# motoko_ice_dragon_x_dc.net
KiCad netlist of a schematic drawn in EAGLE
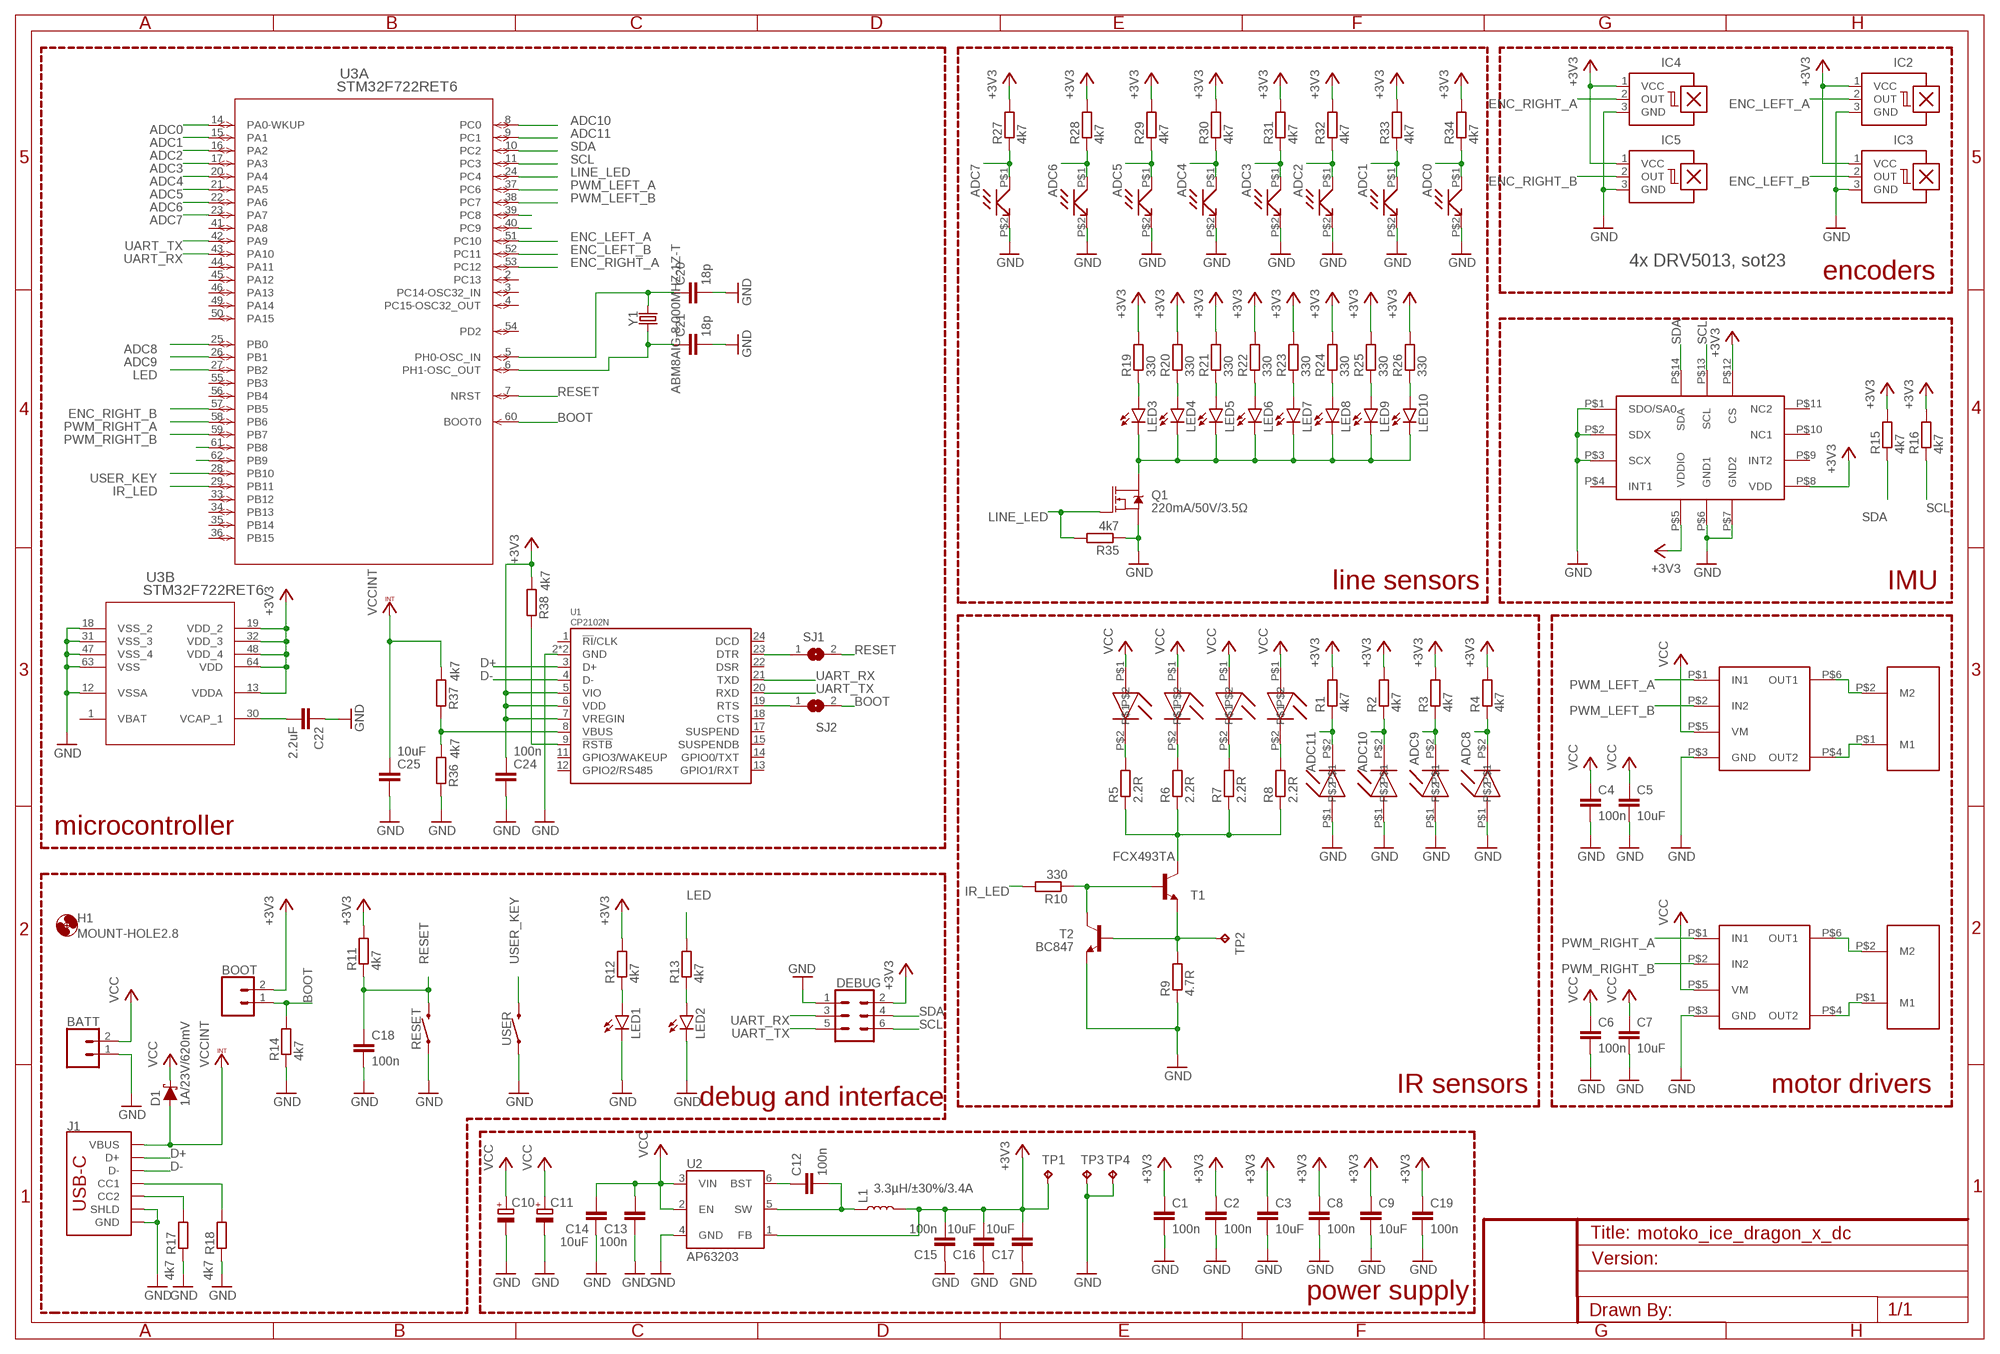
[diagram p0: schematic, sheet 1]

(export (version "E")
  (design (tool "Eeschema 10.0.6"))
  (components
    (comp (ref "BATT")
      (value "CONN_02LOCK_LONGPADS")
      (footprint "eagle-import:1X02_LOCK_LONGPADS")
      (libsource (lib "eagle-import") (part "CONN_02LOCK_LONGPADS"))
    )
    (comp (ref "BOOT")
      (value "CONN_02LOCK_LONGPADS")
      (footprint "eagle-import:1X02_LOCK_LONGPADS")
      (libsource (lib "eagle-import") (part "CONN_02LOCK_LONGPADS"))
    )
    (comp (ref "C1")
      (value "100n")
      (footprint "eagle-import:C0805")
      (libsource (lib "eagle-import") (part "C-EUC0805"))
    )
    (comp (ref "C2")
      (value "100n")
      (footprint "eagle-import:C0805")
      (libsource (lib "eagle-import") (part "C-EUC0805"))
    )
    (comp (ref "C3")
      (value "10uF")
      (footprint "eagle-import:C0805")
      (libsource (lib "eagle-import") (part "C-EUC0805"))
    )
    (comp (ref "C4")
      (value "100n")
      (footprint "eagle-import:C0805")
      (libsource (lib "eagle-import") (part "C-EUC0805"))
    )
    (comp (ref "C5")
      (value "10uF")
      (footprint "eagle-import:C0805")
      (libsource (lib "eagle-import") (part "C-EUC0805"))
    )
    (comp (ref "C6")
      (value "100n")
      (footprint "eagle-import:C0805")
      (libsource (lib "eagle-import") (part "C-EUC0805"))
    )
    (comp (ref "C7")
      (value "10uF")
      (footprint "eagle-import:C0805")
      (libsource (lib "eagle-import") (part "C-EUC0805"))
    )
    (comp (ref "C8")
      (value "100n")
      (footprint "eagle-import:C0805")
      (libsource (lib "eagle-import") (part "C-EUC0805"))
    )
    (comp (ref "C9")
      (value "10uF")
      (footprint "eagle-import:C0805")
      (libsource (lib "eagle-import") (part "C-EUC0805"))
    )
    (comp (ref "C10")
      (value "CPOL-EU140CLH-0810")
      (footprint "eagle-import:140CLH-0810")
      (libsource (lib "eagle-import") (part "CPOL-EU140CLH-0810"))
    )
    (comp (ref "C11")
      (value "CPOL-EU140CLH-0810")
      (footprint "eagle-import:140CLH-0810")
      (libsource (lib "eagle-import") (part "CPOL-EU140CLH-0810"))
    )
    (comp (ref "C12")
      (value "100n")
      (footprint "eagle-import:C0805")
      (libsource (lib "eagle-import") (part "C-EUC0805"))
    )
    (comp (ref "C13")
      (value "100n")
      (footprint "eagle-import:C0805")
      (libsource (lib "eagle-import") (part "C-EUC0805"))
    )
    (comp (ref "C14")
      (value "10uF")
      (footprint "eagle-import:C0805")
      (libsource (lib "eagle-import") (part "C-EUC0805"))
    )
    (comp (ref "C15")
      (value "100n")
      (footprint "eagle-import:C0805")
      (libsource (lib "eagle-import") (part "C-EUC0805"))
    )
    (comp (ref "C16")
      (value "10uF")
      (footprint "eagle-import:C0805")
      (libsource (lib "eagle-import") (part "C-EUC0805"))
    )
    (comp (ref "C17")
      (value "10uF")
      (footprint "eagle-import:C0805")
      (libsource (lib "eagle-import") (part "C-EUC0805"))
    )
    (comp (ref "C18")
      (value "100n")
      (footprint "eagle-import:C0805")
      (libsource (lib "eagle-import") (part "C-EUC0805"))
    )
    (comp (ref "C19")
      (value "100n")
      (footprint "eagle-import:C0805")
      (libsource (lib "eagle-import") (part "C-EUC0805"))
    )
    (comp (ref "C20")
      (value "18p")
      (footprint "eagle-import:C0805")
      (libsource (lib "eagle-import") (part "C-EUC0805"))
    )
    (comp (ref "C21")
      (value "18p")
      (footprint "eagle-import:C0805")
      (libsource (lib "eagle-import") (part "C-EUC0805"))
    )
    (comp (ref "C22")
      (value "2.2uF")
      (footprint "eagle-import:C0805")
      (libsource (lib "eagle-import") (part "C-EUC0805"))
    )
    (comp (ref "C24")
      (value "100n")
      (footprint "eagle-import:C0805")
      (libsource (lib "eagle-import") (part "C-EUC0805"))
    )
    (comp (ref "C25")
      (value "10uF")
      (footprint "eagle-import:C0805")
      (libsource (lib "eagle-import") (part "C-EUC0805"))
    )
    (comp (ref "D1")
      (value "1A/23V/620mV")
      (footprint "eagle-import:SOD-323")
      (libsource (lib "eagle-import") (part "DIODE-SCHOTTKY-BAT20J"))
    )
    (comp (ref "DEBUG")
      (value "FEMALE 2x3")
      (footprint "eagle-import:2X3")
      (libsource (lib "eagle-import") (part "CONN_03X2FEMALE"))
    )
    (comp (ref "H1")
      (value "MOUNT-HOLE2.8")
      (footprint "eagle-import:2,8")
      (libsource (lib "eagle-import") (part "MOUNT-HOLE2.8"))
    )
    (comp (ref "IC2")
      (value "A1202LH")
      (footprint "eagle-import:SOT23-W")
      (libsource (lib "eagle-import") (part "A12?LH02"))
    )
    (comp (ref "IC3")
      (value "A1202LH")
      (footprint "eagle-import:SOT23-W")
      (libsource (lib "eagle-import") (part "A12?LH02"))
    )
    (comp (ref "IC4")
      (value "A1202LH")
      (footprint "eagle-import:SOT23-W")
      (libsource (lib "eagle-import") (part "A12?LH02"))
    )
    (comp (ref "IC5")
      (value "A1202LH")
      (footprint "eagle-import:SOT23-W")
      (libsource (lib "eagle-import") (part "A12?LH02"))
    )
    (comp (ref "J1")
      (value "640-USB4105-GF-A-120, man. GCT")
      (footprint "eagle-import:USB-C-16P-2LAYER-PADS")
      (libsource (lib "eagle-import") (part "USB_C_2-LAYER_PADS"))
    )
    (comp (ref "L1")
      (value "3.3µH/±30%/3.4A")
      (footprint "eagle-import:CR54")
      (libsource (lib "eagle-import") (part "INDUCTOR-CR54-3.3UH"))
    )
    (comp (ref "LED1")
      (value "LEDCHIPLED_1206")
      (footprint "eagle-import:CHIPLED_1206")
      (libsource (lib "eagle-import") (part "LEDCHIPLED_1206"))
    )
    (comp (ref "LED2")
      (value "LEDCHIPLED_1206")
      (footprint "eagle-import:CHIPLED_1206")
      (libsource (lib "eagle-import") (part "LEDCHIPLED_1206"))
    )
    (comp (ref "LED3")
      (value "LEDCHIPLED_1206")
      (footprint "eagle-import:CHIPLED_1206")
      (libsource (lib "eagle-import") (part "LEDCHIPLED_1206"))
    )
    (comp (ref "LED4")
      (value "LEDCHIPLED_1206")
      (footprint "eagle-import:CHIPLED_1206")
      (libsource (lib "eagle-import") (part "LEDCHIPLED_1206"))
    )
    (comp (ref "LED5")
      (value "LEDCHIPLED_1206")
      (footprint "eagle-import:CHIPLED_1206")
      (libsource (lib "eagle-import") (part "LEDCHIPLED_1206"))
    )
    (comp (ref "LED6")
      (value "LEDCHIPLED_1206")
      (footprint "eagle-import:CHIPLED_1206")
      (libsource (lib "eagle-import") (part "LEDCHIPLED_1206"))
    )
    (comp (ref "LED7")
      (value "LEDCHIPLED_1206")
      (footprint "eagle-import:CHIPLED_1206")
      (libsource (lib "eagle-import") (part "LEDCHIPLED_1206"))
    )
    (comp (ref "LED8")
      (value "LEDCHIPLED_1206")
      (footprint "eagle-import:CHIPLED_1206")
      (libsource (lib "eagle-import") (part "LEDCHIPLED_1206"))
    )
    (comp (ref "LED9")
      (value "LEDCHIPLED_1206")
      (footprint "eagle-import:CHIPLED_1206")
      (libsource (lib "eagle-import") (part "LEDCHIPLED_1206"))
    )
    (comp (ref "LED10")
      (value "LEDCHIPLED_1206")
      (footprint "eagle-import:CHIPLED_1206")
      (libsource (lib "eagle-import") (part "LEDCHIPLED_1206"))
    )
    (comp (ref "Q1")
      (value "220mA/50V/3.5Ω")
      (footprint "eagle-import:SOT23-3")
      (libsource (lib "eagle-import") (part "MOSFET-NCH-BSS138"))
    )
    (comp (ref "R1")
      (value "4k7")
      (footprint "eagle-import:M0805")
      (libsource (lib "eagle-import") (part "R-EU_M0805"))
    )
    (comp (ref "R2")
      (value "4k7")
      (footprint "eagle-import:M0805")
      (libsource (lib "eagle-import") (part "R-EU_M0805"))
    )
    (comp (ref "R3")
      (value "4k7")
      (footprint "eagle-import:M0805")
      (libsource (lib "eagle-import") (part "R-EU_M0805"))
    )
    (comp (ref "R4")
      (value "4k7")
      (footprint "eagle-import:M0805")
      (libsource (lib "eagle-import") (part "R-EU_M0805"))
    )
    (comp (ref "R5")
      (value "2.2R")
      (footprint "eagle-import:M0805")
      (libsource (lib "eagle-import") (part "R-EU_M0805"))
    )
    (comp (ref "R6")
      (value "2.2R")
      (footprint "eagle-import:M0805")
      (libsource (lib "eagle-import") (part "R-EU_M0805"))
    )
    (comp (ref "R7")
      (value "2.2R")
      (footprint "eagle-import:M0805")
      (libsource (lib "eagle-import") (part "R-EU_M0805"))
    )
    (comp (ref "R8")
      (value "2.2R")
      (footprint "eagle-import:M0805")
      (libsource (lib "eagle-import") (part "R-EU_M0805"))
    )
    (comp (ref "R9")
      (value "4.7R")
      (footprint "eagle-import:M0805")
      (libsource (lib "eagle-import") (part "R-EU_M0805"))
    )
    (comp (ref "R10")
      (value "330")
      (footprint "eagle-import:M0805")
      (libsource (lib "eagle-import") (part "R-EU_M0805"))
    )
    (comp (ref "R11")
      (value "4k7")
      (footprint "eagle-import:M0805")
      (libsource (lib "eagle-import") (part "R-EU_M0805"))
    )
    (comp (ref "R12")
      (value "4k7")
      (footprint "eagle-import:M0805")
      (libsource (lib "eagle-import") (part "R-EU_M0805"))
    )
    (comp (ref "R13")
      (value "4k7")
      (footprint "eagle-import:M0805")
      (libsource (lib "eagle-import") (part "R-EU_M0805"))
    )
    (comp (ref "R14")
      (value "4k7")
      (footprint "eagle-import:M0805")
      (libsource (lib "eagle-import") (part "R-EU_M0805"))
    )
    (comp (ref "R15")
      (value "4k7")
      (footprint "eagle-import:M0805")
      (libsource (lib "eagle-import") (part "R-EU_M0805"))
    )
    (comp (ref "R16")
      (value "4k7")
      (footprint "eagle-import:M0805")
      (libsource (lib "eagle-import") (part "R-EU_M0805"))
    )
    (comp (ref "R17")
      (value "4k7")
      (footprint "eagle-import:M0805")
      (libsource (lib "eagle-import") (part "R-EU_M0805"))
    )
    (comp (ref "R18")
      (value "4k7")
      (footprint "eagle-import:M0805")
      (libsource (lib "eagle-import") (part "R-EU_M0805"))
    )
    (comp (ref "R19")
      (value "330")
      (footprint "eagle-import:M0805")
      (libsource (lib "eagle-import") (part "R-EU_M0805"))
    )
    (comp (ref "R20")
      (value "330")
      (footprint "eagle-import:M0805")
      (libsource (lib "eagle-import") (part "R-EU_M0805"))
    )
    (comp (ref "R21")
      (value "330")
      (footprint "eagle-import:M0805")
      (libsource (lib "eagle-import") (part "R-EU_M0805"))
    )
    (comp (ref "R22")
      (value "330")
      (footprint "eagle-import:M0805")
      (libsource (lib "eagle-import") (part "R-EU_M0805"))
    )
    (comp (ref "R23")
      (value "330")
      (footprint "eagle-import:M0805")
      (libsource (lib "eagle-import") (part "R-EU_M0805"))
    )
    (comp (ref "R24")
      (value "330")
      (footprint "eagle-import:M0805")
      (libsource (lib "eagle-import") (part "R-EU_M0805"))
    )
    (comp (ref "R25")
      (value "330")
      (footprint "eagle-import:M0805")
      (libsource (lib "eagle-import") (part "R-EU_M0805"))
    )
    (comp (ref "R26")
      (value "330")
      (footprint "eagle-import:M0805")
      (libsource (lib "eagle-import") (part "R-EU_M0805"))
    )
    (comp (ref "R27")
      (value "4k7")
      (footprint "eagle-import:M0805")
      (libsource (lib "eagle-import") (part "R-EU_M0805"))
    )
    (comp (ref "R28")
      (value "4k7")
      (footprint "eagle-import:M0805")
      (libsource (lib "eagle-import") (part "R-EU_M0805"))
    )
    (comp (ref "R29")
      (value "4k7")
      (footprint "eagle-import:M0805")
      (libsource (lib "eagle-import") (part "R-EU_M0805"))
    )
    (comp (ref "R30")
      (value "4k7")
      (footprint "eagle-import:M0805")
      (libsource (lib "eagle-import") (part "R-EU_M0805"))
    )
    (comp (ref "R31")
      (value "4k7")
      (footprint "eagle-import:M0805")
      (libsource (lib "eagle-import") (part "R-EU_M0805"))
    )
    (comp (ref "R32")
      (value "4k7")
      (footprint "eagle-import:M0805")
      (libsource (lib "eagle-import") (part "R-EU_M0805"))
    )
    (comp (ref "R33")
      (value "4k7")
      (footprint "eagle-import:M0805")
      (libsource (lib "eagle-import") (part "R-EU_M0805"))
    )
    (comp (ref "R34")
      (value "4k7")
      (footprint "eagle-import:M0805")
      (libsource (lib "eagle-import") (part "R-EU_M0805"))
    )
    (comp (ref "R35")
      (value "4k7")
      (footprint "eagle-import:M0805")
      (libsource (lib "eagle-import") (part "R-EU_M0805"))
    )
    (comp (ref "R36")
      (value "4k7")
      (footprint "eagle-import:M0805")
      (libsource (lib "eagle-import") (part "R-EU_M0805"))
    )
    (comp (ref "R37")
      (value "4k7")
      (footprint "eagle-import:M0805")
      (libsource (lib "eagle-import") (part "R-EU_M0805"))
    )
    (comp (ref "R38")
      (value "4k7")
      (footprint "eagle-import:M0805")
      (libsource (lib "eagle-import") (part "R-EU_M0805"))
    )
    (comp (ref "RESET")
      (value "MOMENTARY-SWITCH-SPST-SMD-6.2MM-TALL")
      (footprint "eagle-import:TACTILE_SWITCH_SMD_6.2MM_TALL")
      (libsource (lib "eagle-import") (part "MOMENTARY-SWITCH-SPST-SMD-6.2MM-TALL"))
    )
    (comp (ref "SJ1") (value "SJ") (footprint "eagle-import:SJ") (libsource (lib "eagle-import") (part "SJ")))
    (comp (ref "SJ2") (value "SJ") (footprint "eagle-import:SJ") (libsource (lib "eagle-import") (part "SJ")))
    (comp (ref "T1")
      (value "FCX493TA")
      (footprint "eagle-import:SOT89-BCE")
      (libsource (lib "eagle-import") (part "-NPN-SOT89-BCE"))
    )
    (comp (ref "T2")
      (value "BC847")
      (footprint "eagle-import:SOT23")
      (libsource (lib "eagle-import") (part "BC847"))
    )
    (comp (ref "TP1")
      (value "TPB1,27")
      (footprint "eagle-import:B1,27")
      (libsource (lib "eagle-import") (part "TPB1,27"))
    )
    (comp (ref "TP2")
      (value "TPB1,27")
      (footprint "eagle-import:B1,27")
      (libsource (lib "eagle-import") (part "TPB1,27"))
    )
    (comp (ref "TP3")
      (value "TPB1,27")
      (footprint "eagle-import:B1,27")
      (libsource (lib "eagle-import") (part "TPB1,27"))
    )
    (comp (ref "TP4")
      (value "TPB1,27")
      (footprint "eagle-import:B1,27")
      (libsource (lib "eagle-import") (part "TPB1,27"))
    )
    (comp (ref "U$1")
      (value "DRV8212")
      (footprint "eagle-import:SOT_0.6MM")
      (libsource (lib "eagle-import") (part "DRV8212"))
    )
    (comp (ref "U$2")
      (value "SFH3710")
      (footprint "eagle-import:SFH710")
      (libsource (lib "eagle-import") (part "SFH3710"))
    )
    (comp (ref "U$3")
      (value "DRV8212")
      (footprint "eagle-import:SOT_0.6MM")
      (libsource (lib "eagle-import") (part "DRV8212"))
    )
    (comp (ref "U$4")
      (value "POLOLU_MICRO_METAL_GEAR_MOTOR")
      (footprint "eagle-import:POLOLU_MICRO_METAL_GEAR_MOTOR")
      (libsource (lib "eagle-import") (part "POLOLU_MICRO_METAL_GEAR_MOTOR"))
    )
    (comp (ref "U$5")
      (value "POLOLU_MICRO_METAL_GEAR_MOTOR")
      (footprint "eagle-import:POLOLU_MICRO_METAL_GEAR_MOTOR")
      (libsource (lib "eagle-import") (part "POLOLU_MICRO_METAL_GEAR_MOTOR"))
    )
    (comp (ref "U$6")
      (value "LSM6DSM")
      (footprint "eagle-import:LGA14L")
      (libsource (lib "eagle-import") (part "LSM6DSM"))
    )
    (comp (ref "U$7")
      (value "LED_5MM_AXIAL")
      (footprint "eagle-import:LED_5MM_AXIAL")
      (libsource (lib "eagle-import") (part "LED_5MM_AXIAL"))
    )
    (comp (ref "U$8")
      (value "LED_5MM_AXIAL")
      (footprint "eagle-import:LED_5MM_AXIAL")
      (libsource (lib "eagle-import") (part "LED_5MM_AXIAL"))
    )
    (comp (ref "U$9")
      (value "LED_5MM_AXIAL")
      (footprint "eagle-import:LED_5MM_AXIAL")
      (libsource (lib "eagle-import") (part "LED_5MM_AXIAL"))
    )
    (comp (ref "U$10")
      (value "LED_5MM_AXIAL")
      (footprint "eagle-import:LED_5MM_AXIAL")
      (libsource (lib "eagle-import") (part "LED_5MM_AXIAL"))
    )
    (comp (ref "U$11")
      (value "LED_5MM_AXIAL")
      (footprint "eagle-import:LED_5MM_AXIAL")
      (libsource (lib "eagle-import") (part "LED_5MM_AXIAL"))
    )
    (comp (ref "U$12")
      (value "LED_5MM_AXIAL")
      (footprint "eagle-import:LED_5MM_AXIAL")
      (fields (field (name "SPICEPREFIX") "B"))
      (libsource (lib "eagle-import") (part "LED_5MM_AXIAL"))
    )
    (comp (ref "U$13")
      (value "LED_5MM_AXIAL")
      (footprint "eagle-import:LED_5MM_AXIAL")
      (libsource (lib "eagle-import") (part "LED_5MM_AXIAL"))
    )
    (comp (ref "U$14")
      (value "LED_5MM_AXIAL")
      (footprint "eagle-import:LED_5MM_AXIAL")
      (libsource (lib "eagle-import") (part "LED_5MM_AXIAL"))
    )
    (comp (ref "U$15")
      (value "SFH3710")
      (footprint "eagle-import:SFH710")
      (libsource (lib "eagle-import") (part "SFH3710"))
    )
    (comp (ref "U$16")
      (value "SFH3710")
      (footprint "eagle-import:SFH710")
      (libsource (lib "eagle-import") (part "SFH3710"))
    )
    (comp (ref "U$17")
      (value "SFH3710")
      (footprint "eagle-import:SFH710")
      (libsource (lib "eagle-import") (part "SFH3710"))
    )
    (comp (ref "U$18")
      (value "SFH3710")
      (footprint "eagle-import:SFH710")
      (libsource (lib "eagle-import") (part "SFH3710"))
    )
    (comp (ref "U$19")
      (value "SFH3710")
      (footprint "eagle-import:SFH710")
      (libsource (lib "eagle-import") (part "SFH3710"))
    )
    (comp (ref "U$20")
      (value "SFH3710")
      (footprint "eagle-import:SFH710")
      (libsource (lib "eagle-import") (part "SFH3710"))
    )
    (comp (ref "U$21")
      (value "SFH3710")
      (footprint "eagle-import:SFH710")
      (libsource (lib "eagle-import") (part "SFH3710"))
    )
    (comp (ref "U1")
      (value "CP2102N")
      (footprint "eagle-import:QFN24")
      (libsource (lib "eagle-import") (part "CP2102N"))
    )
    (comp (ref "U2")
      (value "AP63203")
      (footprint "eagle-import:SOT23-6")
      (libsource (lib "eagle-import") (part "AP63203"))
    )
    (comp (ref "U3")
      (value "STM32F722RET6")
      (footprint "eagle-import:LQFP64-10X10MM")
      (fields (field (name "COPYRIGHT") "Copyright (C) 2024 Ultra Librarian. All rights reserved."))
      (libsource (lib "eagle-import") (part "STM32F722RET6"))
    )
    (comp (ref "USER")
      (value "MOMENTARY-SWITCH-SPST-SMD-6.2MM-TALL")
      (footprint "eagle-import:TACTILE_SWITCH_SMD_6.2MM_TALL")
      (libsource (lib "eagle-import") (part "MOMENTARY-SWITCH-SPST-SMD-6.2MM-TALL"))
    )
    (comp (ref "Y1")
      (value "ABM8AIG-8.000MHZ-1Z-T")
      (footprint "eagle-import:CRYSTAL-SMD-3.2X2.5MM")
      (libsource (lib "eagle-import") (part "CRYSTALSMD-3.2X2.5"))
    )
  )
  (nets
    (net (code "1") (name "+3V3") (class "Default")
      (node (ref "BOOT") (pin "2") (pinfunction "2_2") (pintype "passive"))
      (node (ref "C1") (pin "1") (pinfunction "1_1") (pintype "passive"))
      (node (ref "C15") (pin "2") (pinfunction "2_2") (pintype "passive"))
      (node (ref "C16") (pin "2") (pinfunction "2_2") (pintype "passive"))
      (node (ref "C17") (pin "2") (pinfunction "2_2") (pintype "passive"))
      (node (ref "C19") (pin "1") (pinfunction "1_1") (pintype "passive"))
      (node (ref "C2") (pin "1") (pinfunction "1_1") (pintype "passive"))
      (node (ref "C24") (pin "1") (pinfunction "1_1") (pintype "passive"))
      (node (ref "C3") (pin "1") (pinfunction "1_1") (pintype "passive"))
      (node (ref "C8") (pin "1") (pinfunction "1_1") (pintype "passive"))
      (node (ref "C9") (pin "1") (pinfunction "1_1") (pintype "passive"))
      (node (ref "DEBUG") (pin "2") (pinfunction "2_2") (pintype "bidirectional"))
      (node (ref "IC2") (pin "1") (pinfunction "VCC_1") (pintype "power_in"))
      (node (ref "IC3") (pin "1") (pinfunction "VCC_1") (pintype "power_in"))
      (node (ref "IC4") (pin "1") (pinfunction "VCC_1") (pintype "power_in"))
      (node (ref "IC5") (pin "1") (pinfunction "VCC_1") (pintype "power_in"))
      (node (ref "L1") (pin "P$2") (pinfunction "2_P$2") (pintype "passive"))
      (node (ref "R1") (pin "2") (pinfunction "2_2") (pintype "passive"))
      (node (ref "R11") (pin "2") (pinfunction "2_2") (pintype "passive"))
      (node (ref "R12") (pin "2") (pinfunction "2_2") (pintype "passive"))
      (node (ref "R15") (pin "2") (pinfunction "2_2") (pintype "passive"))
      (node (ref "R16") (pin "2") (pinfunction "2_2") (pintype "passive"))
      (node (ref "R19") (pin "2") (pinfunction "2_2") (pintype "passive"))
      (node (ref "R2") (pin "2") (pinfunction "2_2") (pintype "passive"))
      (node (ref "R20") (pin "2") (pinfunction "2_2") (pintype "passive"))
      (node (ref "R21") (pin "2") (pinfunction "2_2") (pintype "passive"))
      (node (ref "R22") (pin "2") (pinfunction "2_2") (pintype "passive"))
      (node (ref "R23") (pin "2") (pinfunction "2_2") (pintype "passive"))
      (node (ref "R24") (pin "2") (pinfunction "2_2") (pintype "passive"))
      (node (ref "R25") (pin "2") (pinfunction "2_2") (pintype "passive"))
      (node (ref "R26") (pin "2") (pinfunction "2_2") (pintype "passive"))
      (node (ref "R27") (pin "2") (pinfunction "2_2") (pintype "passive"))
      (node (ref "R28") (pin "2") (pinfunction "2_2") (pintype "passive"))
      (node (ref "R29") (pin "2") (pinfunction "2_2") (pintype "passive"))
      (node (ref "R3") (pin "2") (pinfunction "2_2") (pintype "passive"))
      (node (ref "R30") (pin "2") (pinfunction "2_2") (pintype "passive"))
      (node (ref "R31") (pin "2") (pinfunction "2_2") (pintype "passive"))
      (node (ref "R32") (pin "2") (pinfunction "2_2") (pintype "passive"))
      (node (ref "R33") (pin "2") (pinfunction "2_2") (pintype "passive"))
      (node (ref "R34") (pin "2") (pinfunction "2_2") (pintype "passive"))
      (node (ref "R38") (pin "1") (pinfunction "1_1") (pintype "passive"))
      (node (ref "R4") (pin "2") (pinfunction "2_2") (pintype "passive"))
      (node (ref "TP1") (pin "TP") (pinfunction "TP_TP") (pintype "input"))
      (node (ref "U$6") (pin "P$12") (pinfunction "CS_P$12") (pintype "bidirectional"))
      (node (ref "U$6") (pin "P$5") (pinfunction "VDDIO_P$5") (pintype "bidirectional"))
      (node (ref "U$6") (pin "P$8") (pinfunction "VDD_P$8") (pintype "bidirectional"))
      (node (ref "U1") (pin "5") (pinfunction "VIO_5") (pintype "bidirectional"))
      (node (ref "U1") (pin "6") (pinfunction "VDD_6") (pintype "bidirectional"))
      (node (ref "U1") (pin "7") (pinfunction "VREGIN_7") (pintype "bidirectional"))
      (node (ref "U2") (pin "1") (pinfunction "FB_1") (pintype "bidirectional"))
      (node (ref "U3") (pin "13") (pinfunction "VDDA_13") (pintype "power_in"))
      (node (ref "U3") (pin "19") (pinfunction "VDD_2_19") (pintype "power_in"))
      (node (ref "U3") (pin "32") (pinfunction "VDD_3_32") (pintype "power_in"))
      (node (ref "U3") (pin "48") (pinfunction "VDD_4_48") (pintype "power_in"))
      (node (ref "U3") (pin "64") (pinfunction "VDD_64") (pintype "power_in"))
    )
    (net (code "2") (name "/ADC0") (class "Default")
      (node (ref "R34") (pin "1") (pinfunction "1_1") (pintype "passive"))
      (node (ref "U$21") (pin "P$1") (pinfunction "C_P$1") (pintype "bidirectional"))
      (node (ref "U3") (pin "14") (pinfunction "PA0-WKUP_14") (pintype "bidirectional"))
    )
    (net (code "3") (name "/ADC1") (class "Default")
      (node (ref "R33") (pin "1") (pinfunction "1_1") (pintype "passive"))
      (node (ref "U$20") (pin "P$1") (pinfunction "C_P$1") (pintype "bidirectional"))
      (node (ref "U3") (pin "15") (pinfunction "PA1_15") (pintype "bidirectional"))
    )
    (net (code "4") (name "/ADC2") (class "Default")
      (node (ref "R32") (pin "1") (pinfunction "1_1") (pintype "passive"))
      (node (ref "U$19") (pin "P$1") (pinfunction "C_P$1") (pintype "bidirectional"))
      (node (ref "U3") (pin "16") (pinfunction "PA2_16") (pintype "bidirectional"))
    )
    (net (code "5") (name "/ADC3") (class "Default")
      (node (ref "R31") (pin "1") (pinfunction "1_1") (pintype "passive"))
      (node (ref "U$18") (pin "P$1") (pinfunction "C_P$1") (pintype "bidirectional"))
      (node (ref "U3") (pin "17") (pinfunction "PA3_17") (pintype "bidirectional"))
    )
    (net (code "6") (name "/ADC4") (class "Default")
      (node (ref "R30") (pin "1") (pinfunction "1_1") (pintype "passive"))
      (node (ref "U$17") (pin "P$1") (pinfunction "C_P$1") (pintype "bidirectional"))
      (node (ref "U3") (pin "20") (pinfunction "PA4_20") (pintype "bidirectional"))
    )
    (net (code "7") (name "/ADC5") (class "Default")
      (node (ref "R29") (pin "1") (pinfunction "1_1") (pintype "passive"))
      (node (ref "U$16") (pin "P$1") (pinfunction "C_P$1") (pintype "bidirectional"))
      (node (ref "U3") (pin "21") (pinfunction "PA5_21") (pintype "bidirectional"))
    )
    (net (code "8") (name "/ADC6") (class "Default")
      (node (ref "R28") (pin "1") (pinfunction "1_1") (pintype "passive"))
      (node (ref "U$15") (pin "P$1") (pinfunction "C_P$1") (pintype "bidirectional"))
      (node (ref "U3") (pin "22") (pinfunction "PA6_22") (pintype "bidirectional"))
    )
    (net (code "9") (name "/ADC7") (class "Default")
      (node (ref "R27") (pin "1") (pinfunction "1_1") (pintype "passive"))
      (node (ref "U$2") (pin "P$1") (pinfunction "C_P$1") (pintype "bidirectional"))
      (node (ref "U3") (pin "23") (pinfunction "PA7_23") (pintype "bidirectional"))
    )
    (net (code "10") (name "/ADC8") (class "Default")
      (node (ref "R4") (pin "1") (pinfunction "1_1") (pintype "passive"))
      (node (ref "U$7") (pin "P$2") (pinfunction "P$2_P$2") (pintype "bidirectional"))
      (node (ref "U3") (pin "25") (pinfunction "PB0_25") (pintype "bidirectional"))
    )
    (net (code "11") (name "/ADC9") (class "Default")
      (node (ref "R3") (pin "1") (pinfunction "1_1") (pintype "passive"))
      (node (ref "U$11") (pin "P$2") (pinfunction "P$2_P$2") (pintype "bidirectional"))
      (node (ref "U3") (pin "26") (pinfunction "PB1_26") (pintype "bidirectional"))
    )
    (net (code "12") (name "/ADC10") (class "Default")
      (node (ref "R2") (pin "1") (pinfunction "1_1") (pintype "passive"))
      (node (ref "U$14") (pin "P$2") (pinfunction "P$2_P$2") (pintype "bidirectional"))
      (node (ref "U3") (pin "8") (pinfunction "PC0_8") (pintype "bidirectional"))
    )
    (net (code "13") (name "/ADC11") (class "Default")
      (node (ref "R1") (pin "1") (pinfunction "1_1") (pintype "passive"))
      (node (ref "U$9") (pin "P$2") (pinfunction "P$2_P$2") (pintype "bidirectional"))
      (node (ref "U3") (pin "9") (pinfunction "PC1_9") (pintype "bidirectional"))
    )
    (net (code "14") (name "/BOOT") (class "Default")
      (node (ref "BOOT") (pin "1") (pinfunction "1_1") (pintype "passive"))
      (node (ref "R14") (pin "2") (pinfunction "2_2") (pintype "passive"))
      (node (ref "SJ2") (pin "2") (pinfunction "2_2") (pintype "passive"))
      (node (ref "U3") (pin "60") (pinfunction "BOOT0_60") (pintype "input"))
    )
    (net (code "15") (name "/D+") (class "Default")
      (node (ref "J1") (pin "A6") (pinfunction "D+_A6") (pintype "bidirectional"))
      (node (ref "J1") (pin "B6") (pinfunction "D+_B6") (pintype "bidirectional"))
      (node (ref "U1") (pin "3") (pinfunction "D+_3") (pintype "bidirectional"))
    )
    (net (code "16") (name "/D-") (class "Default")
      (node (ref "J1") (pin "A7") (pinfunction "D-_A7") (pintype "bidirectional"))
      (node (ref "J1") (pin "B7") (pinfunction "D-_B7") (pintype "bidirectional"))
      (node (ref "U1") (pin "4") (pinfunction "D-_4") (pintype "bidirectional"))
    )
    (net (code "17") (name "/ENC_LEFT_A") (class "Default")
      (node (ref "IC2") (pin "2") (pinfunction "OUT_2") (pintype "output"))
      (node (ref "U3") (pin "51") (pinfunction "PC10_51") (pintype "bidirectional"))
    )
    (net (code "18") (name "/ENC_LEFT_B") (class "Default")
      (node (ref "IC3") (pin "2") (pinfunction "OUT_2") (pintype "output"))
      (node (ref "U3") (pin "52") (pinfunction "PC11_52") (pintype "bidirectional"))
    )
    (net (code "19") (name "/ENC_RIGHT_A") (class "Default")
      (node (ref "IC4") (pin "2") (pinfunction "OUT_2") (pintype "output"))
      (node (ref "U3") (pin "53") (pinfunction "PC12_53") (pintype "bidirectional"))
    )
    (net (code "20") (name "/ENC_RIGHT_B") (class "Default")
      (node (ref "IC5") (pin "2") (pinfunction "OUT_2") (pintype "output"))
      (node (ref "U3") (pin "57") (pinfunction "PB5_57") (pintype "bidirectional"))
    )
    (net (code "21") (name "/IR_LED") (class "Default")
      (node (ref "R10") (pin "2") (pinfunction "2_2") (pintype "passive"))
      (node (ref "U3") (pin "29") (pinfunction "PB11_29") (pintype "bidirectional"))
    )
    (net (code "22") (name "/LED") (class "Default")
      (node (ref "R13") (pin "2") (pinfunction "2_2") (pintype "passive"))
      (node (ref "U3") (pin "27") (pinfunction "PB2_27") (pintype "bidirectional"))
    )
    (net (code "23") (name "/LINE_LED") (class "Default")
      (node (ref "Q1") (pin "1") (pinfunction "G_1") (pintype "bidirectional"))
      (node (ref "R35") (pin "2") (pinfunction "2_2") (pintype "passive"))
      (node (ref "U3") (pin "24") (pinfunction "PC4_24") (pintype "bidirectional"))
    )
    (net (code "24") (name "/PWM_LEFT_A") (class "Default")
      (node (ref "U$1") (pin "P$1") (pinfunction "IN1_P$1") (pintype "bidirectional"))
      (node (ref "U3") (pin "37") (pinfunction "PC6_37") (pintype "bidirectional"))
    )
    (net (code "25") (name "/PWM_LEFT_B") (class "Default")
      (node (ref "U$1") (pin "P$2") (pinfunction "IN2_P$2") (pintype "bidirectional"))
      (node (ref "U3") (pin "38") (pinfunction "PC7_38") (pintype "bidirectional"))
    )
    (net (code "26") (name "/PWM_RIGHT_A") (class "Default")
      (node (ref "U$3") (pin "P$1") (pinfunction "IN1_P$1") (pintype "bidirectional"))
      (node (ref "U3") (pin "58") (pinfunction "PB6_58") (pintype "bidirectional"))
    )
    (net (code "27") (name "/PWM_RIGHT_B") (class "Default")
      (node (ref "U$3") (pin "P$2") (pinfunction "IN2_P$2") (pintype "bidirectional"))
      (node (ref "U3") (pin "59") (pinfunction "PB7_59") (pintype "bidirectional"))
    )
    (net (code "28") (name "/RESET") (class "Default")
      (node (ref "C18") (pin "1") (pinfunction "1_1") (pintype "passive"))
      (node (ref "R11") (pin "1") (pinfunction "1_1") (pintype "passive"))
      (node (ref "RESET") (pin "B2") (pinfunction "2_B2") (pintype "passive"))
      (node (ref "SJ1") (pin "2") (pinfunction "2_2") (pintype "passive"))
      (node (ref "U3") (pin "7") (pinfunction "NRST_7") (pintype "bidirectional"))
    )
    (net (code "29") (name "/SCL") (class "Default")
      (node (ref "DEBUG") (pin "6") (pinfunction "6_6") (pintype "bidirectional"))
      (node (ref "R16") (pin "1") (pinfunction "1_1") (pintype "passive"))
      (node (ref "U$6") (pin "P$13") (pinfunction "SCL_P$13") (pintype "bidirectional"))
      (node (ref "U3") (pin "11") (pinfunction "PC3_11") (pintype "bidirectional"))
    )
    (net (code "30") (name "/SDA") (class "Default")
      (node (ref "DEBUG") (pin "4") (pinfunction "4_4") (pintype "bidirectional"))
      (node (ref "R15") (pin "1") (pinfunction "1_1") (pintype "passive"))
      (node (ref "U$6") (pin "P$14") (pinfunction "SDA_P$14") (pintype "bidirectional"))
      (node (ref "U3") (pin "10") (pinfunction "PC2_10") (pintype "bidirectional"))
    )
    (net (code "31") (name "/UART_RX") (class "Default")
      (node (ref "DEBUG") (pin "3") (pinfunction "3_3") (pintype "bidirectional"))
      (node (ref "U1") (pin "21") (pinfunction "TXD_21") (pintype "bidirectional"))
      (node (ref "U3") (pin "43") (pinfunction "PA10_43") (pintype "bidirectional"))
    )
    (net (code "32") (name "/UART_TX") (class "Default")
      (node (ref "DEBUG") (pin "5") (pinfunction "5_5") (pintype "bidirectional"))
      (node (ref "U1") (pin "20") (pinfunction "RXD_20") (pintype "bidirectional"))
      (node (ref "U3") (pin "42") (pinfunction "PA9_42") (pintype "bidirectional"))
    )
    (net (code "33") (name "/USER_KEY") (class "Default")
      (node (ref "U3") (pin "28") (pinfunction "PB10_28") (pintype "bidirectional"))
      (node (ref "USER") (pin "B2") (pinfunction "2_B2") (pintype "passive"))
    )
    (net (code "34") (name "/VBAT") (class "Default")
      (node (ref "U3") (pin "1") (pinfunction "VBAT_1") (pintype "power_in"))
    )
    (net (code "35") (name "GND") (class "Default")
      (node (ref "BATT") (pin "1") (pinfunction "1_1") (pintype "passive"))
      (node (ref "C1") (pin "2") (pinfunction "2_2") (pintype "passive"))
      (node (ref "C10") (pin "-") (pinfunction "-_-") (pintype "passive"))
      (node (ref "C11") (pin "-") (pinfunction "-_-") (pintype "passive"))
      (node (ref "C13") (pin "1") (pinfunction "1_1") (pintype "passive"))
      (node (ref "C14") (pin "1") (pinfunction "1_1") (pintype "passive"))
      (node (ref "C15") (pin "1") (pinfunction "1_1") (pintype "passive"))
      (node (ref "C16") (pin "1") (pinfunction "1_1") (pintype "passive"))
      (node (ref "C17") (pin "1") (pinfunction "1_1") (pintype "passive"))
      (node (ref "C18") (pin "2") (pinfunction "2_2") (pintype "passive"))
      (node (ref "C19") (pin "2") (pinfunction "2_2") (pintype "passive"))
      (node (ref "C2") (pin "2") (pinfunction "2_2") (pintype "passive"))
      (node (ref "C20") (pin "2") (pinfunction "2_2") (pintype "passive"))
      (node (ref "C21") (pin "2") (pinfunction "2_2") (pintype "passive"))
      (node (ref "C22") (pin "1") (pinfunction "1_1") (pintype "passive"))
      (node (ref "C24") (pin "2") (pinfunction "2_2") (pintype "passive"))
      (node (ref "C25") (pin "2") (pinfunction "2_2") (pintype "passive"))
      (node (ref "C3") (pin "2") (pinfunction "2_2") (pintype "passive"))
      (node (ref "C4") (pin "2") (pinfunction "2_2") (pintype "passive"))
      (node (ref "C5") (pin "2") (pinfunction "2_2") (pintype "passive"))
      (node (ref "C6") (pin "2") (pinfunction "2_2") (pintype "passive"))
      (node (ref "C7") (pin "2") (pinfunction "2_2") (pintype "passive"))
      (node (ref "C8") (pin "2") (pinfunction "2_2") (pintype "passive"))
      (node (ref "C9") (pin "2") (pinfunction "2_2") (pintype "passive"))
      (node (ref "DEBUG") (pin "1") (pinfunction "1_1") (pintype "bidirectional"))
      (node (ref "IC2") (pin "3") (pinfunction "GND_3") (pintype "power_in"))
      (node (ref "IC3") (pin "3") (pinfunction "GND_3") (pintype "power_in"))
      (node (ref "IC4") (pin "3") (pinfunction "GND_3") (pintype "power_in"))
      (node (ref "IC5") (pin "3") (pinfunction "GND_3") (pintype "power_in"))
      (node (ref "J1") (pin "GND") (pinfunction "GND_GND") (pintype "bidirectional"))
      (node (ref "J1") (pin "GND2") (pinfunction "GND_GND2") (pintype "bidirectional"))
      (node (ref "J1") (pin "SHLD1") (pinfunction "SHLD_SHLD1") (pintype "bidirectional"))
      (node (ref "J1") (pin "SHLD2") (pinfunction "SHLD_SHLD2") (pintype "bidirectional"))
      (node (ref "J1") (pin "SHLD3") (pinfunction "SHLD_SHLD3") (pintype "bidirectional"))
      (node (ref "J1") (pin "SHLD4") (pinfunction "SHLD_SHLD4") (pintype "bidirectional"))
      (node (ref "LED1") (pin "C") (pinfunction "C_C") (pintype "passive"))
      (node (ref "LED2") (pin "C") (pinfunction "C_C") (pintype "passive"))
      (node (ref "Q1") (pin "2") (pinfunction "S_2") (pintype "bidirectional"))
      (node (ref "R14") (pin "1") (pinfunction "1_1") (pintype "passive"))
      (node (ref "R17") (pin "1") (pinfunction "1_1") (pintype "passive"))
      (node (ref "R18") (pin "1") (pinfunction "1_1") (pintype "passive"))
      (node (ref "R35") (pin "1") (pinfunction "1_1") (pintype "passive"))
      (node (ref "R36") (pin "2") (pinfunction "2_2") (pintype "passive"))
      (node (ref "R9") (pin "1") (pinfunction "1_1") (pintype "passive"))
      (node (ref "RESET") (pin "A2") (pinfunction "1_A2") (pintype "passive"))
      (node (ref "T2") (pin "2") (pinfunction "E_2") (pintype "passive"))
      (node (ref "TP3") (pin "TP") (pinfunction "TP_TP") (pintype "input"))
      (node (ref "TP4") (pin "TP") (pinfunction "TP_TP") (pintype "input"))
      (node (ref "U$1") (pin "P$3") (pinfunction "GND_P$3") (pintype "bidirectional"))
      (node (ref "U$11") (pin "P$1") (pinfunction "P$1_P$1") (pintype "bidirectional"))
      (node (ref "U$14") (pin "P$1") (pinfunction "P$1_P$1") (pintype "bidirectional"))
      (node (ref "U$15") (pin "P$2") (pinfunction "E_P$2") (pintype "bidirectional"))
      (node (ref "U$16") (pin "P$2") (pinfunction "E_P$2") (pintype "bidirectional"))
      (node (ref "U$17") (pin "P$2") (pinfunction "E_P$2") (pintype "bidirectional"))
      (node (ref "U$18") (pin "P$2") (pinfunction "E_P$2") (pintype "bidirectional"))
      (node (ref "U$19") (pin "P$2") (pinfunction "E_P$2") (pintype "bidirectional"))
      (node (ref "U$2") (pin "P$2") (pinfunction "E_P$2") (pintype "bidirectional"))
      (node (ref "U$20") (pin "P$2") (pinfunction "E_P$2") (pintype "bidirectional"))
      (node (ref "U$21") (pin "P$2") (pinfunction "E_P$2") (pintype "bidirectional"))
      (node (ref "U$3") (pin "P$3") (pinfunction "GND_P$3") (pintype "bidirectional"))
      (node (ref "U$6") (pin "P$1") (pinfunction "SDO/SA0_P$1") (pintype "bidirectional"))
      (node (ref "U$6") (pin "P$2") (pinfunction "SDX_P$2") (pintype "bidirectional"))
      (node (ref "U$6") (pin "P$3") (pinfunction "SCX_P$3") (pintype "bidirectional"))
      (node (ref "U$6") (pin "P$6") (pinfunction "GND1_P$6") (pintype "bidirectional"))
      (node (ref "U$6") (pin "P$7") (pinfunction "GND2_P$7") (pintype "bidirectional"))
      (node (ref "U$7") (pin "P$1") (pinfunction "P$1_P$1") (pintype "bidirectional"))
      (node (ref "U$9") (pin "P$1") (pinfunction "P$1_P$1") (pintype "bidirectional"))
      (node (ref "U1") (pin "2") (pinfunction "GND_2") (pintype "bidirectional"))
      (node (ref "U1") (pin "PAD") (pinfunction "GND_PAD") (pintype "bidirectional"))
      (node (ref "U2") (pin "4") (pinfunction "GND_4") (pintype "bidirectional"))
      (node (ref "U3") (pin "12") (pinfunction "VSSA_12") (pintype "power_in"))
      (node (ref "U3") (pin "18") (pinfunction "VSS_2_18") (pintype "power_in"))
      (node (ref "U3") (pin "31") (pinfunction "VSS_3_31") (pintype "power_in"))
      (node (ref "U3") (pin "47") (pinfunction "VSS_4_47") (pintype "power_in"))
      (node (ref "U3") (pin "63") (pinfunction "VSS_63") (pintype "power_in"))
      (node (ref "USER") (pin "A2") (pinfunction "1_A2") (pintype "passive"))
    )
    (net (code "36") (name "Net-(J1-CC1)") (class "Default")
      (node (ref "J1") (pin "A5") (pinfunction "CC1_A5") (pintype "bidirectional"))
      (node (ref "R18") (pin "2") (pinfunction "2_2") (pintype "passive"))
    )
    (net (code "37") (name "Net-(J1-CC2)") (class "Default")
      (node (ref "J1") (pin "B5") (pinfunction "CC2_B5") (pintype "bidirectional"))
      (node (ref "R17") (pin "2") (pinfunction "2_2") (pintype "passive"))
    )
    (net (code "38") (name "Net-(L1-1)") (class "Default")
      (node (ref "C12") (pin "2") (pinfunction "2_2") (pintype "passive"))
      (node (ref "L1") (pin "P$1") (pinfunction "1_P$1") (pintype "passive"))
      (node (ref "U2") (pin "5") (pinfunction "SW_5") (pintype "bidirectional"))
    )
    (net (code "39") (name "Net-(LED1-PadA)") (class "Default")
      (node (ref "LED1") (pin "A") (pinfunction "A_A") (pintype "passive"))
      (node (ref "R12") (pin "1") (pinfunction "1_1") (pintype "passive"))
    )
    (net (code "40") (name "Net-(LED2-PadA)") (class "Default")
      (node (ref "LED2") (pin "A") (pinfunction "A_A") (pintype "passive"))
      (node (ref "R13") (pin "1") (pinfunction "1_1") (pintype "passive"))
    )
    (net (code "41") (name "Net-(LED3-PadA)") (class "Default")
      (node (ref "LED3") (pin "A") (pinfunction "A_A") (pintype "passive"))
      (node (ref "R19") (pin "1") (pinfunction "1_1") (pintype "passive"))
    )
    (net (code "42") (name "Net-(LED4-PadA)") (class "Default")
      (node (ref "LED4") (pin "A") (pinfunction "A_A") (pintype "passive"))
      (node (ref "R20") (pin "1") (pinfunction "1_1") (pintype "passive"))
    )
    (net (code "43") (name "Net-(LED5-PadA)") (class "Default")
      (node (ref "LED5") (pin "A") (pinfunction "A_A") (pintype "passive"))
      (node (ref "R21") (pin "1") (pinfunction "1_1") (pintype "passive"))
    )
    (net (code "44") (name "Net-(LED6-PadA)") (class "Default")
      (node (ref "LED6") (pin "A") (pinfunction "A_A") (pintype "passive"))
      (node (ref "R22") (pin "1") (pinfunction "1_1") (pintype "passive"))
    )
    (net (code "45") (name "Net-(LED7-PadA)") (class "Default")
      (node (ref "LED7") (pin "A") (pinfunction "A_A") (pintype "passive"))
      (node (ref "R23") (pin "1") (pinfunction "1_1") (pintype "passive"))
    )
    (net (code "46") (name "Net-(LED8-PadA)") (class "Default")
      (node (ref "LED8") (pin "A") (pinfunction "A_A") (pintype "passive"))
      (node (ref "R24") (pin "1") (pinfunction "1_1") (pintype "passive"))
    )
    (net (code "47") (name "Net-(LED9-PadA)") (class "Default")
      (node (ref "LED9") (pin "A") (pinfunction "A_A") (pintype "passive"))
      (node (ref "R25") (pin "1") (pinfunction "1_1") (pintype "passive"))
    )
    (net (code "48") (name "Net-(LED10-PadA)") (class "Default")
      (node (ref "LED10") (pin "A") (pinfunction "A_A") (pintype "passive"))
      (node (ref "R26") (pin "1") (pinfunction "1_1") (pintype "passive"))
    )
    (net (code "49") (name "Net-(Q1-D)") (class "Default")
      (node (ref "LED10") (pin "C") (pinfunction "C_C") (pintype "passive"))
      (node (ref "LED3") (pin "C") (pinfunction "C_C") (pintype "passive"))
      (node (ref "LED4") (pin "C") (pinfunction "C_C") (pintype "passive"))
      (node (ref "LED5") (pin "C") (pinfunction "C_C") (pintype "passive"))
      (node (ref "LED6") (pin "C") (pinfunction "C_C") (pintype "passive"))
      (node (ref "LED7") (pin "C") (pinfunction "C_C") (pintype "passive"))
      (node (ref "LED8") (pin "C") (pinfunction "C_C") (pintype "passive"))
      (node (ref "LED9") (pin "C") (pinfunction "C_C") (pintype "passive"))
      (node (ref "Q1") (pin "3") (pinfunction "D_3") (pintype "bidirectional"))
    )
    (net (code "50") (name "Net-(R5-Pad1)") (class "Default")
      (node (ref "R5") (pin "1") (pinfunction "1_1") (pintype "passive"))
      (node (ref "R6") (pin "1") (pinfunction "1_1") (pintype "passive"))
      (node (ref "R7") (pin "1") (pinfunction "1_1") (pintype "passive"))
      (node (ref "R8") (pin "1") (pinfunction "1_1") (pintype "passive"))
      (node (ref "T1") (pin "C") (pinfunction "C_C") (pintype "passive"))
    )
    (net (code "51") (name "Net-(R5-Pad2)") (class "Default")
      (node (ref "R5") (pin "2") (pinfunction "2_2") (pintype "passive"))
      (node (ref "U$10") (pin "P$2") (pinfunction "P$2_P$2") (pintype "bidirectional"))
    )
    (net (code "52") (name "Net-(R6-Pad2)") (class "Default")
      (node (ref "R6") (pin "2") (pinfunction "2_2") (pintype "passive"))
      (node (ref "U$13") (pin "P$2") (pinfunction "P$2_P$2") (pintype "bidirectional"))
    )
    (net (code "53") (name "Net-(R7-Pad2)") (class "Default")
      (node (ref "R7") (pin "2") (pinfunction "2_2") (pintype "passive"))
      (node (ref "U$12") (pin "P$2") (pinfunction "P$2_P$2") (pintype "bidirectional"))
    )
    (net (code "54") (name "Net-(R8-Pad2)") (class "Default")
      (node (ref "R8") (pin "2") (pinfunction "2_2") (pintype "passive"))
      (node (ref "U$8") (pin "P$2") (pinfunction "P$2_P$2") (pintype "bidirectional"))
    )
    (net (code "55") (name "Net-(T2-B)") (class "Default")
      (node (ref "R9") (pin "2") (pinfunction "2_2") (pintype "passive"))
      (node (ref "T1") (pin "E") (pinfunction "E_E") (pintype "passive"))
      (node (ref "T2") (pin "1") (pinfunction "B_1") (pintype "passive"))
      (node (ref "TP2") (pin "TP") (pinfunction "TP_TP") (pintype "input"))
    )
    (net (code "56") (name "Net-(T2-C)") (class "Default")
      (node (ref "R10") (pin "1") (pinfunction "1_1") (pintype "passive"))
      (node (ref "T1") (pin "B") (pinfunction "B_B") (pintype "passive"))
      (node (ref "T2") (pin "3") (pinfunction "C_3") (pintype "passive"))
    )
    (net (code "57") (name "Net-(U$1-OUT1)") (class "Default")
      (node (ref "U$1") (pin "P$6") (pinfunction "OUT1_P$6") (pintype "bidirectional"))
      (node (ref "U$4") (pin "P$2") (pinfunction "M2_P$2") (pintype "bidirectional"))
    )
    (net (code "58") (name "Net-(U$1-OUT2)") (class "Default")
      (node (ref "U$1") (pin "P$4") (pinfunction "OUT2_P$4") (pintype "bidirectional"))
      (node (ref "U$4") (pin "P$1") (pinfunction "M1_P$1") (pintype "bidirectional"))
    )
    (net (code "59") (name "Net-(U$3-OUT1)") (class "Default")
      (node (ref "U$3") (pin "P$6") (pinfunction "OUT1_P$6") (pintype "bidirectional"))
      (node (ref "U$5") (pin "P$2") (pinfunction "M2_P$2") (pintype "bidirectional"))
    )
    (net (code "60") (name "Net-(U$3-OUT2)") (class "Default")
      (node (ref "U$3") (pin "P$4") (pinfunction "OUT2_P$4") (pintype "bidirectional"))
      (node (ref "U$5") (pin "P$1") (pinfunction "M1_P$1") (pintype "bidirectional"))
    )
    (net (code "61") (name "Net-(U1-DTR)") (class "Default")
      (node (ref "SJ1") (pin "1") (pinfunction "1_1") (pintype "passive"))
      (node (ref "U1") (pin "23") (pinfunction "DTR_23") (pintype "bidirectional"))
    )
    (net (code "62") (name "Net-(U1-RTS)") (class "Default")
      (node (ref "SJ2") (pin "1") (pinfunction "1_1") (pintype "passive"))
      (node (ref "U1") (pin "19") (pinfunction "RTS_19") (pintype "bidirectional"))
    )
    (net (code "63") (name "Net-(U1-VBUS)") (class "Default")
      (node (ref "R36") (pin "1") (pinfunction "1_1") (pintype "passive"))
      (node (ref "R37") (pin "2") (pinfunction "2_2") (pintype "passive"))
      (node (ref "U1") (pin "8") (pinfunction "VBUS_8") (pintype "bidirectional"))
    )
    (net (code "64") (name "Net-(U1-~{RSTB})") (class "Default")
      (node (ref "R38") (pin "2") (pinfunction "2_2") (pintype "passive"))
      (node (ref "U1") (pin "9") (pinfunction "~{RSTB}_9") (pintype "bidirectional"))
    )
    (net (code "65") (name "Net-(U2-BST)") (class "Default")
      (node (ref "C12") (pin "1") (pinfunction "1_1") (pintype "passive"))
      (node (ref "U2") (pin "6") (pinfunction "BST_6") (pintype "bidirectional"))
    )
    (net (code "66") (name "Net-(U3A-PH0-OSC_IN)") (class "Default")
      (node (ref "C20") (pin "1") (pinfunction "1_1") (pintype "passive"))
      (node (ref "U3") (pin "5") (pinfunction "PH0-OSC_IN_5") (pintype "bidirectional"))
      (node (ref "Y1") (pin "3") (pinfunction "2_3") (pintype "passive"))
    )
    (net (code "67") (name "Net-(U3A-PH1-OSC_OUT)") (class "Default")
      (node (ref "C21") (pin "1") (pinfunction "1_1") (pintype "passive"))
      (node (ref "U3") (pin "6") (pinfunction "PH1-OSC_OUT_6") (pintype "bidirectional"))
      (node (ref "Y1") (pin "1") (pinfunction "1_1") (pintype "passive"))
    )
    (net (code "68") (name "Net-(U3B-VCAP_1)") (class "Default")
      (node (ref "C22") (pin "2") (pinfunction "2_2") (pintype "passive"))
      (node (ref "U3") (pin "30") (pinfunction "VCAP_1_30") (pintype "power_in"))
    )
    (net (code "69") (name "VCC") (class "Default")
      (node (ref "BATT") (pin "2") (pinfunction "2_2") (pintype "passive"))
      (node (ref "C10") (pin "+") (pinfunction "+_+") (pintype "passive"))
      (node (ref "C11") (pin "+") (pinfunction "+_+") (pintype "passive"))
      (node (ref "C13") (pin "2") (pinfunction "2_2") (pintype "passive"))
      (node (ref "C14") (pin "2") (pinfunction "2_2") (pintype "passive"))
      (node (ref "C4") (pin "1") (pinfunction "1_1") (pintype "passive"))
      (node (ref "C5") (pin "1") (pinfunction "1_1") (pintype "passive"))
      (node (ref "C6") (pin "1") (pinfunction "1_1") (pintype "passive"))
      (node (ref "C7") (pin "1") (pinfunction "1_1") (pintype "passive"))
      (node (ref "D1") (pin "C") (pinfunction "C_C") (pintype "passive"))
      (node (ref "U$1") (pin "P$5") (pinfunction "VM_P$5") (pintype "bidirectional"))
      (node (ref "U$10") (pin "P$1") (pinfunction "P$1_P$1") (pintype "bidirectional"))
      (node (ref "U$12") (pin "P$1") (pinfunction "P$1_P$1") (pintype "bidirectional"))
      (node (ref "U$13") (pin "P$1") (pinfunction "P$1_P$1") (pintype "bidirectional"))
      (node (ref "U$3") (pin "P$5") (pinfunction "VM_P$5") (pintype "bidirectional"))
      (node (ref "U$8") (pin "P$1") (pinfunction "P$1_P$1") (pintype "bidirectional"))
      (node (ref "U2") (pin "2") (pinfunction "EN_2") (pintype "bidirectional"))
      (node (ref "U2") (pin "3") (pinfunction "VIN_3") (pintype "bidirectional"))
    )
    (net (code "70") (name "VCCINT") (class "Default")
      (node (ref "C25") (pin "1") (pinfunction "1_1") (pintype "passive"))
      (node (ref "D1") (pin "A") (pinfunction "A_A") (pintype "passive"))
      (node (ref "J1") (pin "VBUS1") (pinfunction "VBUS_VBUS1") (pintype "bidirectional"))
      (node (ref "J1") (pin "VBUS2") (pinfunction "VBUS_VBUS2") (pintype "bidirectional"))
      (node (ref "R37") (pin "1") (pinfunction "1_1") (pintype "passive"))
    )
    (net (code "71") (name "unconnected-(U$6-INT1-PadP$4)") (class "Default")
      (node (ref "U$6") (pin "P$4") (pinfunction "INT1_P$4") (pintype "bidirectional"))
    )
    (net (code "72") (name "unconnected-(U$6-INT2-PadP$9)") (class "Default")
      (node (ref "U$6") (pin "P$9") (pinfunction "INT2_P$9") (pintype "bidirectional"))
    )
    (net (code "73") (name "unconnected-(U$6-NC1-PadP$10)") (class "Default")
      (node (ref "U$6") (pin "P$10") (pinfunction "NC1_P$10") (pintype "bidirectional"))
    )
    (net (code "74") (name "unconnected-(U$6-NC2-PadP$11)") (class "Default")
      (node (ref "U$6") (pin "P$11") (pinfunction "NC2_P$11") (pintype "bidirectional"))
    )
    (net (code "75") (name "unconnected-(U1-CTS-Pad18)") (class "Default")
      (node (ref "U1") (pin "18") (pinfunction "CTS_18") (pintype "bidirectional"))
    )
    (net (code "76") (name "unconnected-(U1-DCD-Pad24)") (class "Default")
      (node (ref "U1") (pin "24") (pinfunction "DCD_24") (pintype "bidirectional"))
    )
    (net (code "77") (name "unconnected-(U1-DSR-Pad22)") (class "Default")
      (node (ref "U1") (pin "22") (pinfunction "DSR_22") (pintype "bidirectional"))
    )
    (net (code "78") (name "unconnected-(U1-GPIO0{slash}TXT-Pad14)") (class "Default")
      (node (ref "U1") (pin "14") (pinfunction "GPIO0/TXT_14") (pintype "bidirectional"))
    )
    (net (code "79") (name "unconnected-(U1-GPIO1{slash}RXT-Pad13)") (class "Default")
      (node (ref "U1") (pin "13") (pinfunction "GPIO1/RXT_13") (pintype "bidirectional"))
    )
    (net (code "80") (name "unconnected-(U1-GPIO2{slash}RS485-Pad12)") (class "Default")
      (node (ref "U1") (pin "12") (pinfunction "GPIO2/RS485_12") (pintype "bidirectional"))
    )
    (net (code "81") (name "unconnected-(U1-GPIO3{slash}WAKEUP-Pad11)") (class "Default")
      (node (ref "U1") (pin "11") (pinfunction "GPIO3/WAKEUP_11") (pintype "bidirectional"))
    )
    (net (code "82") (name "unconnected-(U1-SUSPEND-Pad17)") (class "Default")
      (node (ref "U1") (pin "17") (pinfunction "SUSPEND_17") (pintype "bidirectional"))
    )
    (net (code "83") (name "unconnected-(U1-SUSPENDB-Pad15)") (class "Default")
      (node (ref "U1") (pin "15") (pinfunction "SUSPENDB_15") (pintype "bidirectional"))
    )
    (net (code "84") (name "unconnected-(U1-~{RI}{slash}CLK-Pad1)") (class "Default")
      (node (ref "U1") (pin "1") (pinfunction "~{RI}/CLK_1") (pintype "bidirectional"))
    )
    (net (code "85") (name "unconnected-(U3A-PA8-Pad41)") (class "Default")
      (node (ref "U3") (pin "41") (pinfunction "PA8_41") (pintype "bidirectional"))
    )
    (net (code "86") (name "unconnected-(U3A-PA11-Pad44)") (class "Default")
      (node (ref "U3") (pin "44") (pinfunction "PA11_44") (pintype "bidirectional"))
    )
    (net (code "87") (name "unconnected-(U3A-PA12-Pad45)") (class "Default")
      (node (ref "U3") (pin "45") (pinfunction "PA12_45") (pintype "bidirectional"))
    )
    (net (code "88") (name "unconnected-(U3A-PA13-Pad46)") (class "Default")
      (node (ref "U3") (pin "46") (pinfunction "PA13_46") (pintype "bidirectional"))
    )
    (net (code "89") (name "unconnected-(U3A-PA14-Pad49)") (class "Default")
      (node (ref "U3") (pin "49") (pinfunction "PA14_49") (pintype "bidirectional"))
    )
    (net (code "90") (name "unconnected-(U3A-PA15-Pad50)") (class "Default")
      (node (ref "U3") (pin "50") (pinfunction "PA15_50") (pintype "bidirectional"))
    )
    (net (code "91") (name "unconnected-(U3A-PB3-Pad55)") (class "Default")
      (node (ref "U3") (pin "55") (pinfunction "PB3_55") (pintype "bidirectional"))
    )
    (net (code "92") (name "unconnected-(U3A-PB4-Pad56)") (class "Default")
      (node (ref "U3") (pin "56") (pinfunction "PB4_56") (pintype "bidirectional"))
    )
    (net (code "93") (name "unconnected-(U3A-PB8-Pad61)") (class "Default")
      (node (ref "U3") (pin "61") (pinfunction "PB8_61") (pintype "bidirectional"))
    )
    (net (code "94") (name "unconnected-(U3A-PB9-Pad62)") (class "Default")
      (node (ref "U3") (pin "62") (pinfunction "PB9_62") (pintype "bidirectional"))
    )
    (net (code "95") (name "unconnected-(U3A-PB12-Pad33)") (class "Default")
      (node (ref "U3") (pin "33") (pinfunction "PB12_33") (pintype "bidirectional"))
    )
    (net (code "96") (name "unconnected-(U3A-PB13-Pad34)") (class "Default")
      (node (ref "U3") (pin "34") (pinfunction "PB13_34") (pintype "bidirectional"))
    )
    (net (code "97") (name "unconnected-(U3A-PB14-Pad35)") (class "Default")
      (node (ref "U3") (pin "35") (pinfunction "PB14_35") (pintype "bidirectional"))
    )
    (net (code "98") (name "unconnected-(U3A-PB15-Pad36)") (class "Default")
      (node (ref "U3") (pin "36") (pinfunction "PB15_36") (pintype "bidirectional"))
    )
    (net (code "99") (name "unconnected-(U3A-PC8-Pad39)") (class "Default")
      (node (ref "U3") (pin "39") (pinfunction "PC8_39") (pintype "bidirectional"))
    )
    (net (code "100") (name "unconnected-(U3A-PC9-Pad40)") (class "Default")
      (node (ref "U3") (pin "40") (pinfunction "PC9_40") (pintype "bidirectional"))
    )
    (net (code "101") (name "unconnected-(U3A-PC13-Pad2)") (class "Default")
      (node (ref "U3") (pin "2") (pinfunction "PC13_2") (pintype "bidirectional"))
    )
    (net (code "102") (name "unconnected-(U3A-PC14-OSC32_IN-Pad3)") (class "Default")
      (node (ref "U3") (pin "3") (pinfunction "PC14-OSC32_IN_3") (pintype "bidirectional"))
    )
    (net (code "103") (name "unconnected-(U3A-PC15-OSC32_OUT-Pad4)") (class "Default")
      (node (ref "U3") (pin "4") (pinfunction "PC15-OSC32_OUT_4") (pintype "bidirectional"))
    )
    (net (code "104") (name "unconnected-(U3A-PD2-Pad54)") (class "Default")
      (node (ref "U3") (pin "54") (pinfunction "PD2_54") (pintype "bidirectional"))
    )
  )
)
